# leiterplatte_kuechenlicht.net
KiCad netlist of a schematic drawn in EAGLE
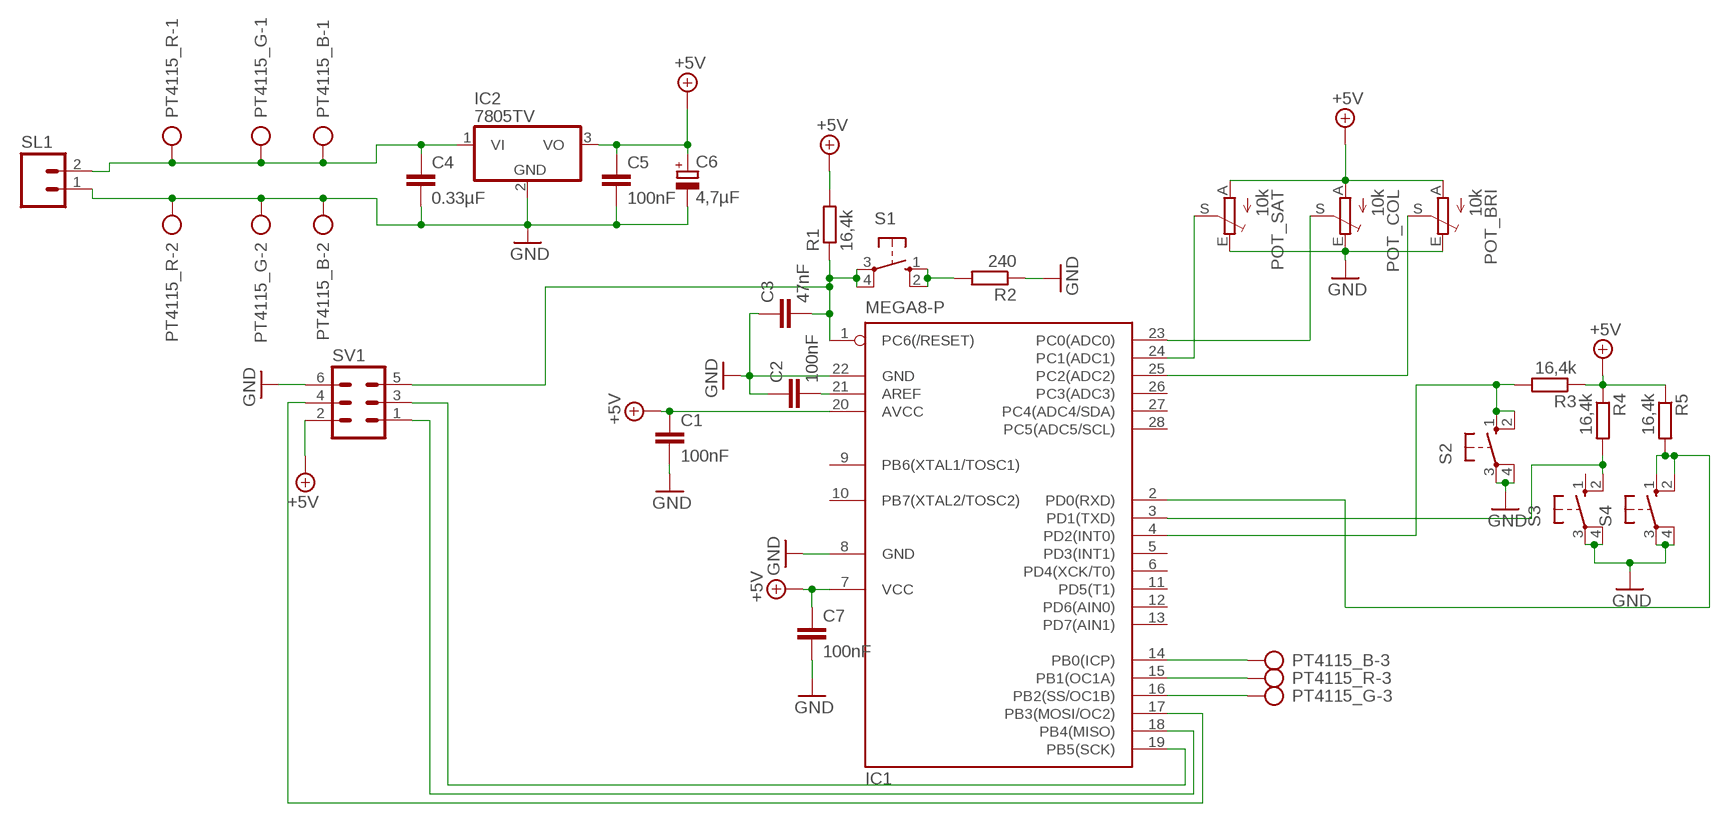
[diagram p0: schematic, sheet 1]

(export (version "E")
  (design (tool "Eeschema 10.0.6"))
  (components
    (comp (ref "C1")
      (value "100nF")
      (footprint "eagle-import:C2.5-3")
      (libsource (lib "eagle-import") (part "C2,5-3"))
    )
    (comp (ref "C2")
      (value "100nF")
      (footprint "eagle-import:C2.5-3")
      (libsource (lib "eagle-import") (part "C2,5-3"))
    )
    (comp (ref "C3")
      (value "47nF")
      (footprint "eagle-import:C050-025X075")
      (libsource (lib "eagle-import") (part "C-EU050-025X075"))
    )
    (comp (ref "C4")
      (value "0.33µF")
      (footprint "eagle-import:C2.5-3")
      (libsource (lib "eagle-import") (part "C2,5-3"))
    )
    (comp (ref "C5")
      (value "100nF")
      (footprint "eagle-import:C2.5-3")
      (libsource (lib "eagle-import") (part "C2,5-3"))
    )
    (comp (ref "C6")
      (value "4,7µF")
      (footprint "eagle-import:E2,5-6E")
      (libsource (lib "eagle-import") (part "CPOL-EUE2,5-6E"))
    )
    (comp (ref "C7")
      (value "100nF")
      (footprint "eagle-import:C2.5-3")
      (libsource (lib "eagle-import") (part "C2,5-3"))
    )
    (comp (ref "IC1")
      (value "MEGA8-P")
      (footprint "eagle-import:DIL28-3")
      (libsource (lib "eagle-import") (part "MEGA8-P"))
    )
    (comp (ref "IC2")
      (value "7805TV")
      (footprint "eagle-import:TO220V")
      (libsource (lib "eagle-import") (part "78TV05"))
    )
    (comp (ref "POT_BRI")
      (value "10k")
      (footprint "eagle-import:CIP20C-6MM")
      (libsource (lib "eagle-import") (part "TRIM_EU-CIP20C-6MM"))
    )
    (comp (ref "POT_COL")
      (value "10k")
      (footprint "eagle-import:CIP20C-6MM")
      (libsource (lib "eagle-import") (part "TRIM_EU-CIP20C-6MM"))
    )
    (comp (ref "POT_SAT")
      (value "10k")
      (footprint "eagle-import:CIP20C-6MM")
      (libsource (lib "eagle-import") (part "TRIM_EU-CIP20C-6MM"))
    )
    (comp (ref "PT4115_B")
      (value "AK300/3")
      (footprint "eagle-import:AK300_3")
      (libsource (lib "eagle-import") (part "AK300/3"))
    )
    (comp (ref "PT4115_G")
      (value "AK300/3")
      (footprint "eagle-import:AK300_3")
      (libsource (lib "eagle-import") (part "AK300/3"))
    )
    (comp (ref "PT4115_R")
      (value "AK300/3")
      (footprint "eagle-import:AK300_3")
      (libsource (lib "eagle-import") (part "AK300/3"))
    )
    (comp (ref "R1")
      (value "16,4k")
      (footprint "eagle-import:0204_7")
      (libsource (lib "eagle-import") (part "R-EU_0204/7"))
    )
    (comp (ref "R2")
      (value "240")
      (footprint "eagle-import:0204_7")
      (libsource (lib "eagle-import") (part "R-EU_0204/7"))
    )
    (comp (ref "R3")
      (value "16,4k")
      (footprint "eagle-import:0204_7")
      (libsource (lib "eagle-import") (part "R-EU_0204/7"))
    )
    (comp (ref "R4")
      (value "16,4k")
      (footprint "eagle-import:0204_7")
      (libsource (lib "eagle-import") (part "R-EU_0204/7"))
    )
    (comp (ref "R5")
      (value "16,4k")
      (footprint "eagle-import:0204_7")
      (libsource (lib "eagle-import") (part "R-EU_0204/7"))
    )
    (comp (ref "S1")
      (value "10-XX")
      (footprint "eagle-import:B3F-10XX")
      (fields (field (name "MPN") "B3F-1000"))
      (libsource (lib "eagle-import") (part "10-XX"))
    )
    (comp (ref "S2")
      (value "10-XX")
      (footprint "eagle-import:B3F-10XX")
      (fields (field (name "MPN") "B3F-1000"))
      (libsource (lib "eagle-import") (part "10-XX"))
    )
    (comp (ref "S3")
      (value "10-XX")
      (footprint "eagle-import:B3F-10XX")
      (fields (field (name "MPN") "B3F-1000"))
      (libsource (lib "eagle-import") (part "10-XX"))
    )
    (comp (ref "S4")
      (value "10-XX")
      (footprint "eagle-import:B3F-10XX")
      (fields (field (name "MPN") "B3F-1000"))
      (libsource (lib "eagle-import") (part "10-XX"))
    )
    (comp (ref "SL1")
      (value "M02")
      (footprint "eagle-import:02P")
      (libsource (lib "eagle-import") (part "M02"))
    )
    (comp (ref "SV1")
      (value "ML6")
      (footprint "eagle-import:ML6")
      (libsource (lib "eagle-import") (part "ML6"))
    )
  )
  (nets
    (net (code "1") (name "+5V") (class "Default")
      (node (ref "C1") (pin "1") (pinfunction "1_1") (pintype "passive"))
      (node (ref "C5") (pin "1") (pinfunction "1_1") (pintype "passive"))
      (node (ref "C6") (pin "+") (pinfunction "+_+") (pintype "passive"))
      (node (ref "C7") (pin "1") (pinfunction "1_1") (pintype "passive"))
      (node (ref "IC1") (pin "20") (pinfunction "AVCC_20") (pintype "power_in"))
      (node (ref "IC1") (pin "7") (pinfunction "VCC_7") (pintype "power_in"))
      (node (ref "IC2") (pin "3") (pinfunction "VO_3") (pintype "passive"))
      (node (ref "POT_BRI") (pin "A") (pinfunction "A_A") (pintype "passive"))
      (node (ref "POT_COL") (pin "A") (pinfunction "A_A") (pintype "passive"))
      (node (ref "POT_SAT") (pin "A") (pinfunction "A_A") (pintype "passive"))
      (node (ref "R1") (pin "2") (pinfunction "2_2") (pintype "passive"))
      (node (ref "R3") (pin "1") (pinfunction "1_1") (pintype "passive"))
      (node (ref "R4") (pin "1") (pinfunction "1_1") (pintype "passive"))
      (node (ref "R5") (pin "1") (pinfunction "1_1") (pintype "passive"))
      (node (ref "SV1") (pin "2") (pinfunction "2_2") (pintype "passive"))
    )
    (net (code "2") (name "GND") (class "Default")
      (node (ref "C1") (pin "2") (pinfunction "2_2") (pintype "passive"))
      (node (ref "C2") (pin "1") (pinfunction "1_1") (pintype "passive"))
      (node (ref "C3") (pin "1") (pinfunction "1_1") (pintype "passive"))
      (node (ref "C4") (pin "2") (pinfunction "2_2") (pintype "passive"))
      (node (ref "C5") (pin "2") (pinfunction "2_2") (pintype "passive"))
      (node (ref "C6") (pin "-") (pinfunction "-_-") (pintype "passive"))
      (node (ref "C7") (pin "2") (pinfunction "2_2") (pintype "passive"))
      (node (ref "IC1") (pin "22") (pinfunction "GND_22") (pintype "power_in"))
      (node (ref "IC1") (pin "8") (pinfunction "GND_8") (pintype "power_in"))
      (node (ref "IC2") (pin "2") (pinfunction "GND_2") (pintype "passive"))
      (node (ref "POT_BRI") (pin "E") (pinfunction "E_E") (pintype "passive"))
      (node (ref "POT_COL") (pin "E") (pinfunction "E_E") (pintype "passive"))
      (node (ref "POT_SAT") (pin "E") (pinfunction "E_E") (pintype "passive"))
      (node (ref "PT4115_B") (pin "2") (pinfunction "KL_2") (pintype "passive"))
      (node (ref "PT4115_G") (pin "2") (pinfunction "KL_2") (pintype "passive"))
      (node (ref "PT4115_R") (pin "2") (pinfunction "KL_2") (pintype "passive"))
      (node (ref "R2") (pin "1") (pinfunction "1_1") (pintype "passive"))
      (node (ref "S2") (pin "3") (pinfunction "P_3") (pintype "passive"))
      (node (ref "S2") (pin "4") (pinfunction "P1_4") (pintype "passive"))
      (node (ref "S3") (pin "3") (pinfunction "P_3") (pintype "passive"))
      (node (ref "S3") (pin "4") (pinfunction "P1_4") (pintype "passive"))
      (node (ref "S4") (pin "3") (pinfunction "P_3") (pintype "passive"))
      (node (ref "S4") (pin "4") (pinfunction "P1_4") (pintype "passive"))
      (node (ref "SL1") (pin "1") (pinfunction "1_1") (pintype "passive"))
      (node (ref "SV1") (pin "6") (pinfunction "6_6") (pintype "passive"))
    )
    (net (code "3") (name "Net-(IC1-AREF)") (class "Default")
      (node (ref "C2") (pin "2") (pinfunction "2_2") (pintype "passive"))
      (node (ref "IC1") (pin "21") (pinfunction "AREF_21") (pintype "passive"))
    )
    (net (code "4") (name "Net-(IC1-PB0(ICP))") (class "Default")
      (node (ref "IC1") (pin "14") (pinfunction "PB0(ICP)_14") (pintype "bidirectional"))
      (node (ref "PT4115_B") (pin "3") (pinfunction "KL_3") (pintype "passive"))
    )
    (net (code "5") (name "Net-(IC1-PB1(OC1A))") (class "Default")
      (node (ref "IC1") (pin "15") (pinfunction "PB1(OC1A)_15") (pintype "bidirectional"))
      (node (ref "PT4115_R") (pin "3") (pinfunction "KL_3") (pintype "passive"))
    )
    (net (code "6") (name "Net-(IC1-PB2(SS{slash}OC1B))") (class "Default")
      (node (ref "IC1") (pin "16") (pinfunction "PB2(SS/OC1B)_16") (pintype "bidirectional"))
      (node (ref "PT4115_G") (pin "3") (pinfunction "KL_3") (pintype "passive"))
    )
    (net (code "7") (name "Net-(IC1-PB3(MOSI{slash}OC2))") (class "Default")
      (node (ref "IC1") (pin "17") (pinfunction "PB3(MOSI/OC2)_17") (pintype "bidirectional"))
      (node (ref "SV1") (pin "4") (pinfunction "4_4") (pintype "passive"))
    )
    (net (code "8") (name "Net-(IC1-PB4(MISO))") (class "Default")
      (node (ref "IC1") (pin "18") (pinfunction "PB4(MISO)_18") (pintype "bidirectional"))
      (node (ref "SV1") (pin "1") (pinfunction "1_1") (pintype "passive"))
    )
    (net (code "9") (name "Net-(IC1-PB5(SCK))") (class "Default")
      (node (ref "IC1") (pin "19") (pinfunction "PB5(SCK)_19") (pintype "bidirectional"))
      (node (ref "SV1") (pin "3") (pinfunction "3_3") (pintype "passive"))
    )
    (net (code "10") (name "Net-(IC1-PC0(ADC0))") (class "Default")
      (node (ref "IC1") (pin "23") (pinfunction "PC0(ADC0)_23") (pintype "bidirectional"))
      (node (ref "POT_COL") (pin "S") (pinfunction "S_S") (pintype "passive"))
    )
    (net (code "11") (name "Net-(IC1-PC1(ADC1))") (class "Default")
      (node (ref "IC1") (pin "24") (pinfunction "PC1(ADC1)_24") (pintype "bidirectional"))
      (node (ref "POT_SAT") (pin "S") (pinfunction "S_S") (pintype "passive"))
    )
    (net (code "12") (name "Net-(IC1-PC2(ADC2))") (class "Default")
      (node (ref "IC1") (pin "25") (pinfunction "PC2(ADC2)_25") (pintype "bidirectional"))
      (node (ref "POT_BRI") (pin "S") (pinfunction "S_S") (pintype "passive"))
    )
    (net (code "13") (name "Net-(IC1-PC6({slash}RESET))") (class "Default")
      (node (ref "C3") (pin "2") (pinfunction "2_2") (pintype "passive"))
      (node (ref "IC1") (pin "1") (pinfunction "PC6(/RESET)_1") (pintype "bidirectional"))
      (node (ref "R1") (pin "1") (pinfunction "1_1") (pintype "passive"))
      (node (ref "S1") (pin "3") (pinfunction "P_3") (pintype "passive"))
      (node (ref "S1") (pin "4") (pinfunction "P1_4") (pintype "passive"))
      (node (ref "SV1") (pin "5") (pinfunction "5_5") (pintype "passive"))
    )
    (net (code "14") (name "Net-(IC1-PD0(RXD))") (class "Default")
      (node (ref "IC1") (pin "2") (pinfunction "PD0(RXD)_2") (pintype "bidirectional"))
      (node (ref "R5") (pin "2") (pinfunction "2_2") (pintype "passive"))
      (node (ref "S4") (pin "1") (pinfunction "S_1") (pintype "passive"))
      (node (ref "S4") (pin "2") (pinfunction "S1_2") (pintype "passive"))
    )
    (net (code "15") (name "Net-(IC1-PD1(TXD))") (class "Default")
      (node (ref "IC1") (pin "3") (pinfunction "PD1(TXD)_3") (pintype "bidirectional"))
      (node (ref "R4") (pin "2") (pinfunction "2_2") (pintype "passive"))
      (node (ref "S3") (pin "2") (pinfunction "S1_2") (pintype "passive"))
    )
    (net (code "16") (name "Net-(IC1-PD2(INT0))") (class "Default")
      (node (ref "IC1") (pin "4") (pinfunction "PD2(INT0)_4") (pintype "bidirectional"))
      (node (ref "R3") (pin "2") (pinfunction "2_2") (pintype "passive"))
      (node (ref "S2") (pin "1") (pinfunction "S_1") (pintype "passive"))
      (node (ref "S2") (pin "2") (pinfunction "S1_2") (pintype "passive"))
    )
    (net (code "17") (name "Net-(IC2-VI)") (class "Default")
      (node (ref "C4") (pin "1") (pinfunction "1_1") (pintype "passive"))
      (node (ref "IC2") (pin "1") (pinfunction "VI_1") (pintype "input"))
      (node (ref "PT4115_B") (pin "1") (pinfunction "KL_1") (pintype "passive"))
      (node (ref "PT4115_G") (pin "1") (pinfunction "KL_1") (pintype "passive"))
      (node (ref "PT4115_R") (pin "1") (pinfunction "KL_1") (pintype "passive"))
      (node (ref "SL1") (pin "2") (pinfunction "2_2") (pintype "passive"))
    )
    (net (code "18") (name "Net-(S1-S)") (class "Default")
      (node (ref "R2") (pin "2") (pinfunction "2_2") (pintype "passive"))
      (node (ref "S1") (pin "1") (pinfunction "S_1") (pintype "passive"))
      (node (ref "S1") (pin "2") (pinfunction "S1_2") (pintype "passive"))
    )
    (net (code "19") (name "unconnected-(IC1-PB6(XTAL1{slash}TOSC1)-Pad9)") (class "Default")
      (node (ref "IC1") (pin "9") (pinfunction "PB6(XTAL1/TOSC1)_9") (pintype "bidirectional"))
    )
    (net (code "20") (name "unconnected-(IC1-PB7(XTAL2{slash}TOSC2)-Pad10)") (class "Default")
      (node (ref "IC1") (pin "10") (pinfunction "PB7(XTAL2/TOSC2)_10") (pintype "bidirectional"))
    )
    (net (code "21") (name "unconnected-(IC1-PC3(ADC3)-Pad26)") (class "Default")
      (node (ref "IC1") (pin "26") (pinfunction "PC3(ADC3)_26") (pintype "bidirectional"))
    )
    (net (code "22") (name "unconnected-(IC1-PC4(ADC4{slash}SDA)-Pad27)") (class "Default")
      (node (ref "IC1") (pin "27") (pinfunction "PC4(ADC4/SDA)_27") (pintype "bidirectional"))
    )
    (net (code "23") (name "unconnected-(IC1-PC5(ADC5{slash}SCL)-Pad28)") (class "Default")
      (node (ref "IC1") (pin "28") (pinfunction "PC5(ADC5/SCL)_28") (pintype "bidirectional"))
    )
    (net (code "24") (name "unconnected-(IC1-PD3(INT1)-Pad5)") (class "Default")
      (node (ref "IC1") (pin "5") (pinfunction "PD3(INT1)_5") (pintype "bidirectional"))
    )
    (net (code "25") (name "unconnected-(IC1-PD4(XCK{slash}T0)-Pad6)") (class "Default")
      (node (ref "IC1") (pin "6") (pinfunction "PD4(XCK/T0)_6") (pintype "bidirectional"))
    )
    (net (code "26") (name "unconnected-(IC1-PD5(T1)-Pad11)") (class "Default")
      (node (ref "IC1") (pin "11") (pinfunction "PD5(T1)_11") (pintype "bidirectional"))
    )
    (net (code "27") (name "unconnected-(IC1-PD6(AIN0)-Pad12)") (class "Default")
      (node (ref "IC1") (pin "12") (pinfunction "PD6(AIN0)_12") (pintype "bidirectional"))
    )
    (net (code "28") (name "unconnected-(IC1-PD7(AIN1)-Pad13)") (class "Default")
      (node (ref "IC1") (pin "13") (pinfunction "PD7(AIN1)_13") (pintype "bidirectional"))
    )
    (net (code "29") (name "unconnected-(S3-S-Pad1)") (class "Default")
      (node (ref "S3") (pin "1") (pinfunction "S_1") (pintype "passive"))
    )
  )
)
